# dboard_eagle_1.net
KiCad netlist of a schematic drawn in Altium Designer
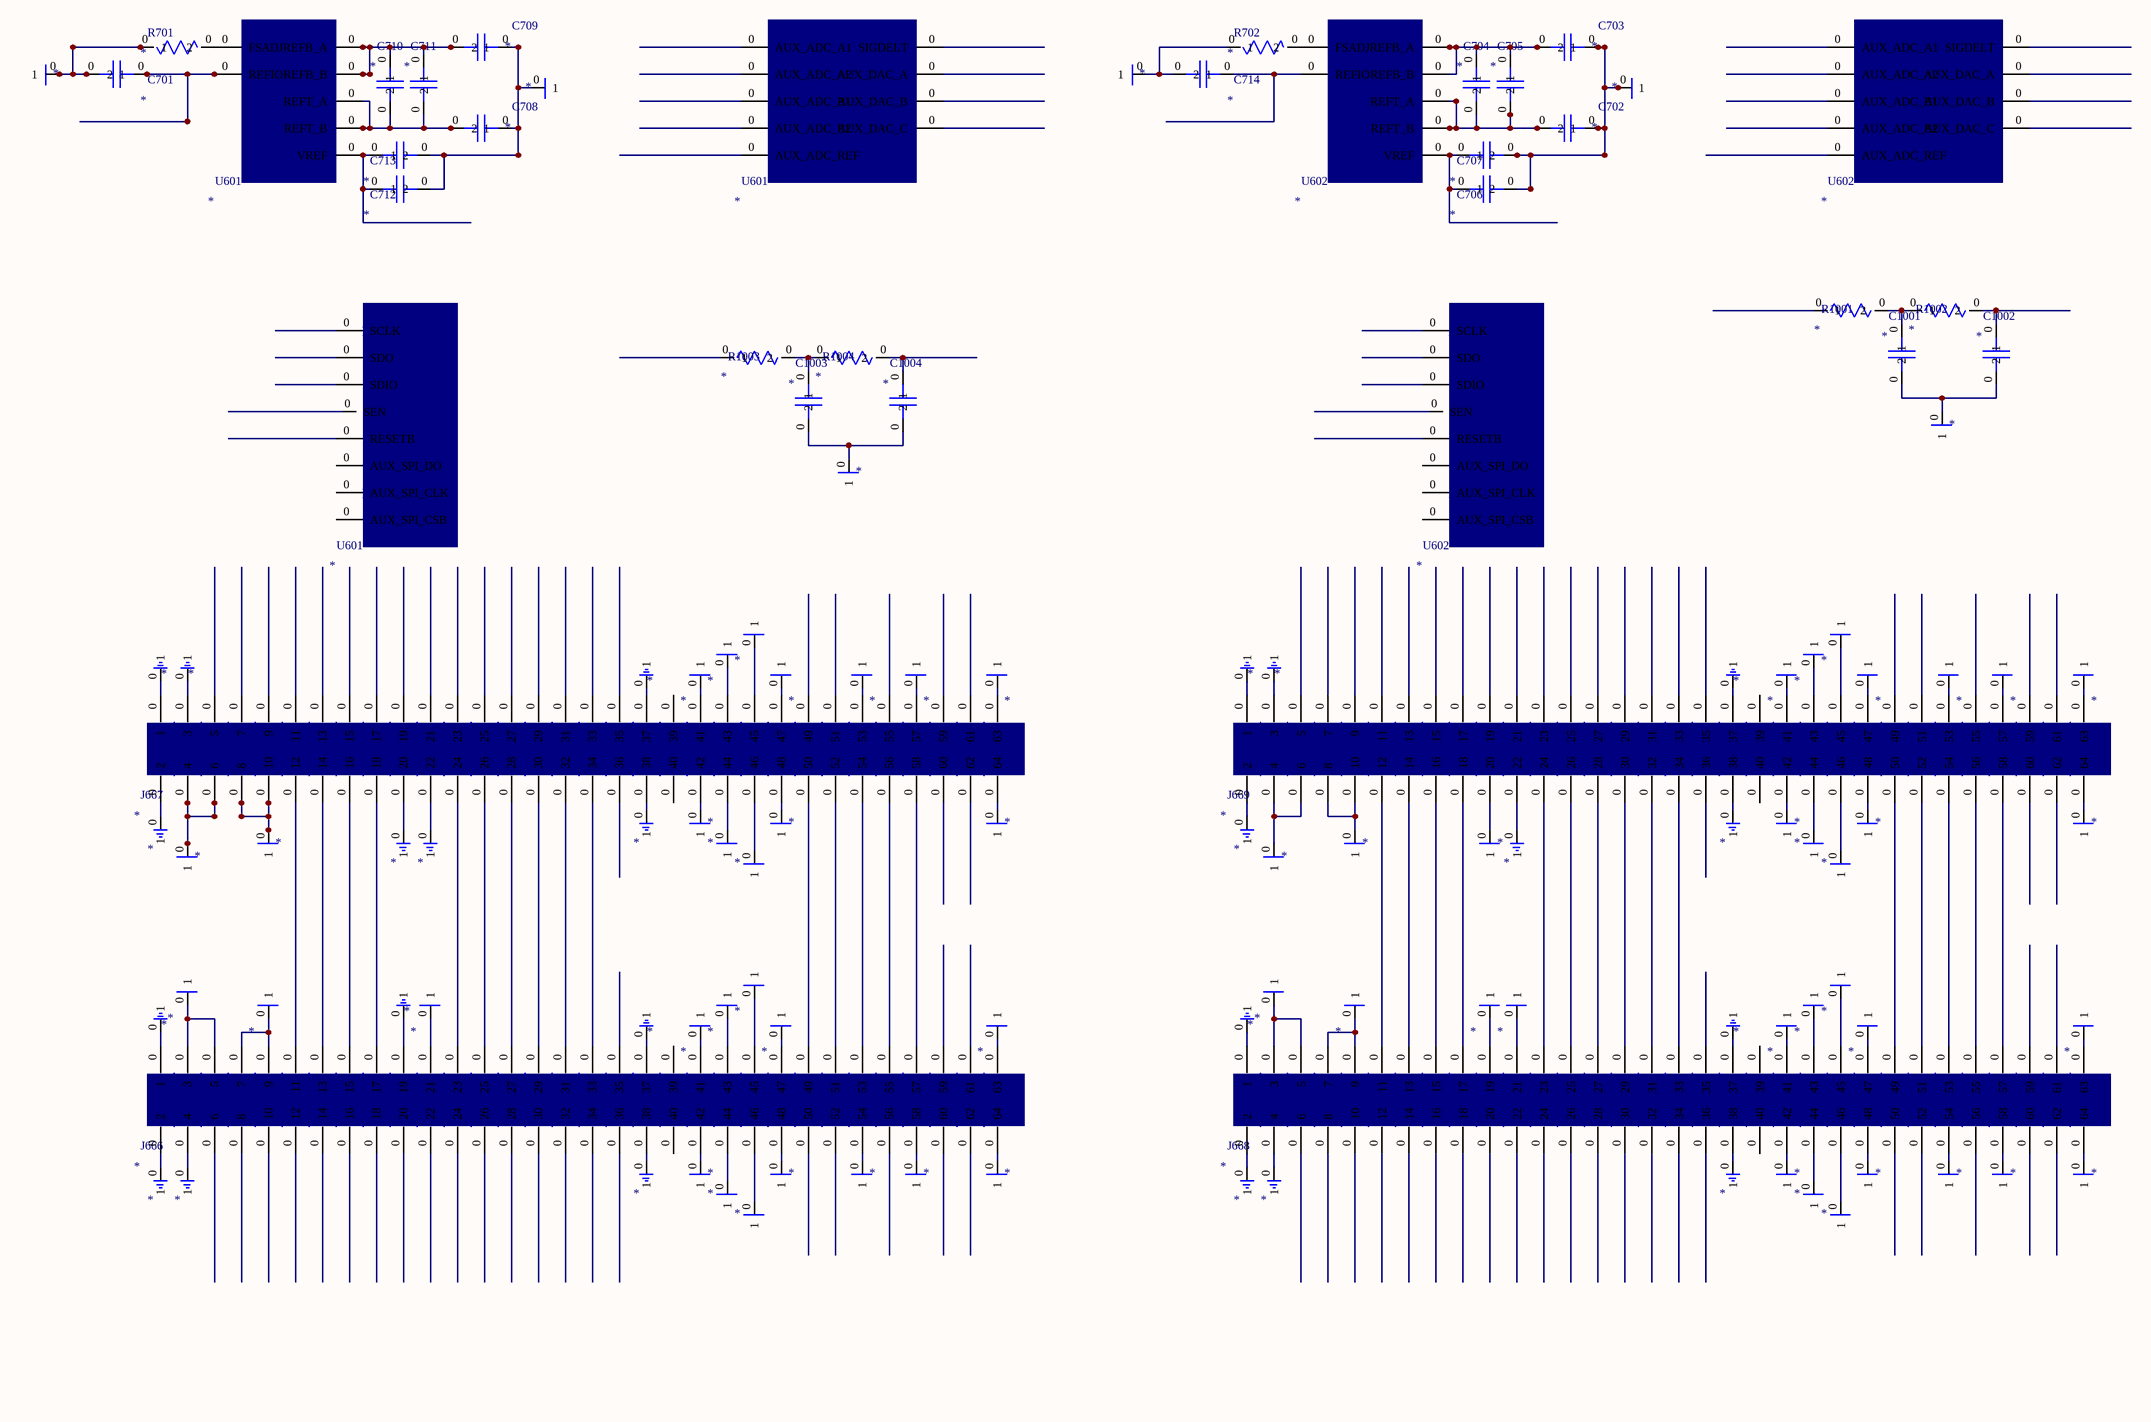
[diagram p0: dboard_eagle_1.SchDoc]

(export (version "E")
  (design (tool "Eeschema 10.0.6"))
  (components
    (comp (ref "C701") (value "*") (libsource (lib "") (part "CAPACITOR-1_MIRRORED_1")))
    (comp (ref "C702") (value "*") (libsource (lib "") (part "CAPACITOR-1_15")))
    (comp (ref "C703") (value "*") (libsource (lib "") (part "CAPACITOR-1_8")))
    (comp (ref "C704") (value "*") (libsource (lib "") (part "CAPACITOR-1_10")))
    (comp (ref "C705") (value "*") (libsource (lib "") (part "CAPACITOR-1_3")))
    (comp (ref "C706") (value "*") (libsource (lib "") (part "CAPACITOR-1_7")))
    (comp (ref "C707") (value "*") (libsource (lib "") (part "CAPACITOR-1_14")))
    (comp (ref "C708") (value "*") (libsource (lib "") (part "CAPACITOR-1_5")))
    (comp (ref "C709") (value "*") (libsource (lib "") (part "CAPACITOR-1_13")))
    (comp (ref "C710") (value "*") (libsource (lib "") (part "CAPACITOR-1_4")))
    (comp (ref "C711") (value "*") (libsource (lib "openjson") (part "CAPACITOR-1")))
    (comp (ref "C712") (value "*") (libsource (lib "") (part "CAPACITOR-1_1")))
    (comp (ref "C713") (value "*") (libsource (lib "") (part "CAPACITOR-1_9")))
    (comp (ref "C714") (value "*") (libsource (lib "openjson") (part "CAPACITOR-1_MIRRORED")))
    (comp (ref "C1001") (value "*") (libsource (lib "") (part "CAPACITOR-1_6")))
    (comp (ref "C1002") (value "*") (libsource (lib "") (part "CAPACITOR-1_11")))
    (comp (ref "C1003") (value "*") (libsource (lib "") (part "CAPACITOR-1_12")))
    (comp (ref "C1004") (value "*") (libsource (lib "") (part "CAPACITOR-1_2")))
    (comp (ref "GENERIC-POWER") (value "*") (libsource (lib "openjson") (part "GENERIC-POWER")))
    (comp (ref "GENERIC-POWER-2") (value "*") (libsource (lib "openjson") (part "GENERIC-POWER")))
    (comp (ref "GENERIC-POWER-3") (value "*") (libsource (lib "openjson") (part "GENERIC-POWER")))
    (comp (ref "GENERIC-POWER-4") (value "*") (libsource (lib "") (part "GENERIC-POWER_1")))
    (comp (ref "GENERIC-POWER-9") (value "*") (libsource (lib "openjson") (part "GENERIC-POWER")))
    (comp (ref "GENERIC-POWER-10") (value "*") (libsource (lib "") (part "GENERIC-POWER_1")))
    (comp (ref "GENERIC-POWER-15") (value "*") (libsource (lib "openjson") (part "GENERIC-POWER")))
    (comp (ref "GENERIC-POWER-16") (value "*") (libsource (lib "openjson") (part "GENERIC-POWER")))
    (comp (ref "GENERIC-POWER-17") (value "*") (libsource (lib "") (part "GENERIC-POWER_1")))
    (comp (ref "GENERIC-POWER-18") (value "*") (libsource (lib "") (part "GENERIC-POWER_1")))
    (comp (ref "GENERIC-POWER-19") (value "*") (libsource (lib "openjson") (part "GENERIC-POWER")))
    (comp (ref "GENERIC-POWER-20") (value "*") (libsource (lib "openjson") (part "GENERIC-POWER")))
    (comp (ref "GENERIC-POWER-21") (value "*") (libsource (lib "openjson") (part "GENERIC-POWER")))
    (comp (ref "GENERIC-POWER-26") (value "*") (libsource (lib "openjson") (part "GENERIC-POWER")))
    (comp (ref "GENERIC-POWER-27") (value "*") (libsource (lib "") (part "GENERIC-POWER_1")))
    (comp (ref "GENERIC-POWER-28") (value "*") (libsource (lib "") (part "GENERIC-POWER_1")))
    (comp (ref "GENERIC-POWER-29") (value "*") (libsource (lib "") (part "GENERIC-POWER_1")))
    (comp (ref "GENERIC-POWER-32") (value "*") (libsource (lib "") (part "GENERIC-POWER_1")))
    (comp (ref "GENERIC-POWER-35") (value "*") (libsource (lib "") (part "GENERIC-POWER_1")))
    (comp (ref "GENERIC-POWER-36") (value "*") (libsource (lib "") (part "GENERIC-POWER_1")))
    (comp (ref "GENERIC-POWER-37") (value "*") (libsource (lib "openjson") (part "GENERIC-POWER")))
    (comp (ref "GENERIC-POWER-38") (value "*") (libsource (lib "") (part "GENERIC-POWER_1")))
    (comp (ref "GENERIC-POWER-42") (value "*") (libsource (lib "openjson") (part "GENERIC-POWER")))
    (comp (ref "GENERIC-POWER-43") (value "*") (libsource (lib "openjson") (part "GENERIC-POWER")))
    (comp (ref "GENERIC-POWER-44") (value "*") (libsource (lib "openjson") (part "GENERIC-POWER")))
    (comp (ref "GENERIC-POWER-48") (value "*") (libsource (lib "") (part "GENERIC-POWER_1")))
    (comp (ref "GENERIC-POWER-53") (value "*") (libsource (lib "openjson") (part "GENERIC-POWER")))
    (comp (ref "GENERIC-POWER-54") (value "*") (libsource (lib "") (part "GENERIC-POWER_1")))
    (comp (ref "GENERIC-POWER-59") (value "*") (libsource (lib "openjson") (part "GENERIC-POWER")))
    (comp (ref "GENERIC-POWER-60") (value "*") (libsource (lib "openjson") (part "GENERIC-POWER")))
    (comp (ref "GENERIC-POWER-61") (value "*") (libsource (lib "") (part "GENERIC-POWER_1")))
    (comp (ref "GENERIC-POWER-62") (value "*") (libsource (lib "") (part "GENERIC-POWER_1")))
    (comp (ref "GENERIC-POWER-63") (value "*") (libsource (lib "openjson") (part "GENERIC-POWER")))
    (comp (ref "GENERIC-POWER-64") (value "*") (libsource (lib "openjson") (part "GENERIC-POWER")))
    (comp (ref "GENERIC-POWER-65") (value "*") (libsource (lib "openjson") (part "GENERIC-POWER")))
    (comp (ref "GENERIC-POWER-70") (value "*") (libsource (lib "openjson") (part "GENERIC-POWER")))
    (comp (ref "GENERIC-POWER-71") (value "*") (libsource (lib "") (part "GENERIC-POWER_1")))
    (comp (ref "GENERIC-POWER-72") (value "*") (libsource (lib "") (part "GENERIC-POWER_1")))
    (comp (ref "GENERIC-POWER-73") (value "*") (libsource (lib "") (part "GENERIC-POWER_1")))
    (comp (ref "GENERIC-POWER-76") (value "*") (libsource (lib "") (part "GENERIC-POWER_1")))
    (comp (ref "GENERIC-POWER-79") (value "*") (libsource (lib "") (part "GENERIC-POWER_1")))
    (comp (ref "GENERIC-POWER-80") (value "*") (libsource (lib "") (part "GENERIC-POWER_1")))
    (comp (ref "GENERIC-POWER-81") (value "*") (libsource (lib "openjson") (part "GENERIC-POWER")))
    (comp (ref "GENERIC-POWER-82") (value "*") (libsource (lib "") (part "GENERIC-POWER_1")))
    (comp (ref "GENERIC-POWER-83") (value "*") (libsource (lib "") (part "GENERIC-POWER_1")))
    (comp (ref "GENERIC-POWER-84") (value "*") (libsource (lib "openjson") (part "GENERIC-POWER")))
    (comp (ref "GENERIC-POWER-85") (value "*") (libsource (lib "openjson") (part "GENERIC-POWER")))
    (comp (ref "GENERIC-POWER-86") (value "*") (libsource (lib "openjson") (part "GENERIC-POWER")))
    (comp (ref "GENERIC-POWER_MIRRORED") (value "*") (libsource (lib "") (part "GENERIC-POWER_MIRRORED_1")))
    (comp (ref "GENERIC-POWER_MIRRORED-22")
      (value "*")
      (libsource (lib "") (part "GENERIC-POWER_MIRRORED_1"))
    )
    (comp (ref "GENERIC-POWER_MIRRORED-23")
      (value "*")
      (libsource (lib "") (part "GENERIC-POWER_MIRRORED_1"))
    )
    (comp (ref "GENERIC-POWER_MIRRORED-24")
      (value "*")
      (libsource (lib "") (part "GENERIC-POWER_MIRRORED_1"))
    )
    (comp (ref "GENERIC-POWER_MIRRORED-25")
      (value "*")
      (libsource (lib "") (part "GENERIC-POWER_MIRRORED_1"))
    )
    (comp (ref "GENERIC-POWER_MIRRORED-30")
      (value "*")
      (libsource (lib "openjson") (part "GENERIC-POWER_MIRRORED"))
    )
    (comp (ref "GENERIC-POWER_MIRRORED-31")
      (value "*")
      (libsource (lib "openjson") (part "GENERIC-POWER_MIRRORED"))
    )
    (comp (ref "GENERIC-POWER_MIRRORED-33")
      (value "*")
      (libsource (lib "openjson") (part "GENERIC-POWER_MIRRORED"))
    )
    (comp (ref "GENERIC-POWER_MIRRORED-34")
      (value "*")
      (libsource (lib "openjson") (part "GENERIC-POWER_MIRRORED"))
    )
    (comp (ref "GENERIC-POWER_MIRRORED-41")
      (value "*")
      (libsource (lib "") (part "GENERIC-POWER_MIRRORED_1"))
    )
    (comp (ref "GENERIC-POWER_MIRRORED-66")
      (value "*")
      (libsource (lib "") (part "GENERIC-POWER_MIRRORED_1"))
    )
    (comp (ref "GENERIC-POWER_MIRRORED-67")
      (value "*")
      (libsource (lib "") (part "GENERIC-POWER_MIRRORED_1"))
    )
    (comp (ref "GENERIC-POWER_MIRRORED-68")
      (value "*")
      (libsource (lib "") (part "GENERIC-POWER_MIRRORED_1"))
    )
    (comp (ref "GENERIC-POWER_MIRRORED-69")
      (value "*")
      (libsource (lib "") (part "GENERIC-POWER_MIRRORED_1"))
    )
    (comp (ref "GENERIC-POWER_MIRRORED-74")
      (value "*")
      (libsource (lib "openjson") (part "GENERIC-POWER_MIRRORED"))
    )
    (comp (ref "GENERIC-POWER_MIRRORED-75")
      (value "*")
      (libsource (lib "openjson") (part "GENERIC-POWER_MIRRORED"))
    )
    (comp (ref "GENERIC-POWER_MIRRORED-77")
      (value "*")
      (libsource (lib "openjson") (part "GENERIC-POWER_MIRRORED"))
    )
    (comp (ref "GENERIC-POWER_MIRRORED-78")
      (value "*")
      (libsource (lib "openjson") (part "GENERIC-POWER_MIRRORED"))
    )
    (comp (ref "GND-1") (value "*") (libsource (lib "openjson") (part "GND-1")))
    (comp (ref "GND-1-5") (value "*") (libsource (lib "") (part "GND-1_1")))
    (comp (ref "GND-1-6") (value "*") (libsource (lib "") (part "GND-1_1")))
    (comp (ref "GND-1-7") (value "*") (libsource (lib "openjson") (part "GND-1")))
    (comp (ref "GND-1-8") (value "*") (libsource (lib "openjson") (part "GND-1")))
    (comp (ref "GND-1-11") (value "*") (libsource (lib "openjson") (part "GND-1")))
    (comp (ref "GND-1-12") (value "*") (libsource (lib "") (part "GND-1_1")))
    (comp (ref "GND-1-13") (value "*") (libsource (lib "openjson") (part "GND-1")))
    (comp (ref "GND-1-14") (value "*") (libsource (lib "") (part "GND-1_1")))
    (comp (ref "GND-1-45") (value "*") (libsource (lib "openjson") (part "GND-1")))
    (comp (ref "GND-1-46") (value "*") (libsource (lib "openjson") (part "GND-1")))
    (comp (ref "GND-1-47") (value "*") (libsource (lib "") (part "GND-1_1")))
    (comp (ref "GND-1-49") (value "*") (libsource (lib "") (part "GND-1_1")))
    (comp (ref "GND-1-50") (value "*") (libsource (lib "") (part "GND-1_1")))
    (comp (ref "GND-1-51") (value "*") (libsource (lib "openjson") (part "GND-1")))
    (comp (ref "GND-1-52") (value "*") (libsource (lib "openjson") (part "GND-1")))
    (comp (ref "GND-1-55") (value "*") (libsource (lib "openjson") (part "GND-1")))
    (comp (ref "GND-1-56") (value "*") (libsource (lib "") (part "GND-1_1")))
    (comp (ref "GND-1-57") (value "*") (libsource (lib "openjson") (part "GND-1")))
    (comp (ref "GND-1-58") (value "*") (libsource (lib "") (part "GND-1_1")))
    (comp (ref "GND-1-87") (value "*") (libsource (lib "") (part "GND-1_1")))
    (comp (ref "GND-1-88") (value "*") (libsource (lib "openjson") (part "GND-1")))
    (comp (ref "GND-1-89") (value "*") (libsource (lib "") (part "GND-1_1")))
    (comp (ref "GND-1-90") (value "*") (libsource (lib "openjson") (part "GND-1")))
    (comp (ref "J666") (value "*") (libsource (lib "") (part "PMC64_MIRRORED_2")))
    (comp (ref "J667") (value "*") (libsource (lib "") (part "PMC64_MIRRORED_1")))
    (comp (ref "J668") (value "*") (libsource (lib "") (part "PMC64_MIRRORED_3")))
    (comp (ref "J669") (value "*") (libsource (lib "openjson") (part "PMC64_MIRRORED")))
    (comp (ref "R701") (value "*") (libsource (lib "openjson") (part "RESISTOR-1_MIRRORED")))
    (comp (ref "R702") (value "*") (libsource (lib "") (part "RESISTOR-1_MIRRORED_1")))
    (comp (ref "R1001") (value "*") (libsource (lib "") (part "RESISTOR-1_2")))
    (comp (ref "R1002") (value "*") (libsource (lib "openjson") (part "RESISTOR-1")))
    (comp (ref "R1003") (value "*") (libsource (lib "") (part "RESISTOR-1_3")))
    (comp (ref "R1004") (value "*") (libsource (lib "") (part "RESISTOR-1_1")))
    (comp (ref "U601") (value "*") (libsource (lib "") (part "AD986X-ACTRL_1")))
    (comp (ref "U601-39") (value "*") (libsource (lib "") (part "AD986X-AUX_1")))
    (comp (ref "U601-40") (value "*") (libsource (lib "") (part "AD986X-CTRL_1")))
    (comp (ref "U602") (value "*") (libsource (lib "openjson") (part "AD986X-ACTRL")))
    (comp (ref "U602-0") (value "*") (libsource (lib "openjson") (part "AD986X-AUX")))
    (comp (ref "U602-1") (value "*") (libsource (lib "openjson") (part "AD986X-CTRL")))
  )
  (nets
    (net (code "1") (name "Net-(C701-1)") (class "Default")
      (node (ref "C701") (pin "0") (pinfunction "1_0") (pintype "passive"))
      (node (ref "U601") (pin "0") (pinfunction "REFIO_0") (pintype "passive"))
    )
    (net (code "2") (name "Net-(C701-2)") (class "Default")
      (node (ref "C701") (pin "0") (pinfunction "2_0") (pintype "passive"))
      (node (ref "GENERIC-POWER_MIRRORED-41") (pin "0") (pinfunction "1_0") (pintype "passive"))
      (node (ref "R701") (pin "0") (pinfunction "1_0") (pintype "passive"))
    )
    (net (code "3") (name "Net-(C702-1)") (class "Default")
      (node (ref "C702") (pin "0") (pinfunction "1_0") (pintype "passive"))
      (node (ref "C703") (pin "0") (pinfunction "1_0") (pintype "passive"))
      (node (ref "C706") (pin "0") (pinfunction "2_0") (pintype "passive"))
      (node (ref "C707") (pin "0") (pinfunction "2_0") (pintype "passive"))
      (node (ref "GENERIC-POWER") (pin "0") (pinfunction "1_0") (pintype "passive"))
    )
    (net (code "4") (name "Net-(C702-2)") (class "Default")
      (node (ref "C702") (pin "0") (pinfunction "2_0") (pintype "passive"))
      (node (ref "C704") (pin "0") (pinfunction "2_0") (pintype "passive"))
      (node (ref "C705") (pin "0") (pinfunction "2_0") (pintype "passive"))
      (node (ref "U602") (pin "0") (pinfunction "REFT_A_0") (pintype "passive"))
    )
    (net (code "5") (name "Net-(C703-2)") (class "Default")
      (node (ref "C703") (pin "0") (pinfunction "2_0") (pintype "passive"))
      (node (ref "C704") (pin "0") (pinfunction "1_0") (pintype "passive"))
      (node (ref "C705") (pin "0") (pinfunction "1_0") (pintype "passive"))
      (node (ref "U602") (pin "0") (pinfunction "REFB_A_0") (pintype "passive"))
    )
    (net (code "6") (name "Net-(C706-1)") (class "Default")
      (node (ref "C706") (pin "0") (pinfunction "1_0") (pintype "passive"))
      (node (ref "C707") (pin "0") (pinfunction "1_0") (pintype "passive"))
      (node (ref "U602") (pin "0") (pinfunction "VREF_0") (pintype "passive"))
    )
    (net (code "7") (name "Net-(C708-1)") (class "Default")
      (node (ref "C708") (pin "0") (pinfunction "1_0") (pintype "passive"))
      (node (ref "C709") (pin "0") (pinfunction "1_0") (pintype "passive"))
      (node (ref "C712") (pin "0") (pinfunction "2_0") (pintype "passive"))
      (node (ref "C713") (pin "0") (pinfunction "2_0") (pintype "passive"))
      (node (ref "GENERIC-POWER-42") (pin "0") (pinfunction "1_0") (pintype "passive"))
    )
    (net (code "8") (name "Net-(C708-2)") (class "Default")
      (node (ref "C708") (pin "0") (pinfunction "2_0") (pintype "passive"))
      (node (ref "C710") (pin "0") (pinfunction "2_0") (pintype "passive"))
      (node (ref "C711") (pin "0") (pinfunction "2_0") (pintype "passive"))
      (node (ref "U601") (pin "0") (pinfunction "REFT_A_0") (pintype "passive"))
    )
    (net (code "9") (name "Net-(C709-2)") (class "Default")
      (node (ref "C709") (pin "0") (pinfunction "2_0") (pintype "passive"))
      (node (ref "C710") (pin "0") (pinfunction "1_0") (pintype "passive"))
      (node (ref "C711") (pin "0") (pinfunction "1_0") (pintype "passive"))
      (node (ref "U601") (pin "0") (pinfunction "REFB_A_0") (pintype "passive"))
    )
    (net (code "10") (name "Net-(C712-1)") (class "Default")
      (node (ref "C712") (pin "0") (pinfunction "1_0") (pintype "passive"))
      (node (ref "C713") (pin "0") (pinfunction "1_0") (pintype "passive"))
      (node (ref "U601") (pin "0") (pinfunction "VREF_0") (pintype "passive"))
    )
    (net (code "11") (name "Net-(C714-1)") (class "Default")
      (node (ref "C714") (pin "0") (pinfunction "1_0") (pintype "passive"))
      (node (ref "U602") (pin "0") (pinfunction "REFIO_0") (pintype "passive"))
    )
    (net (code "12") (name "Net-(C714-2)") (class "Default")
      (node (ref "C714") (pin "0") (pinfunction "2_0") (pintype "passive"))
      (node (ref "GENERIC-POWER_MIRRORED") (pin "0") (pinfunction "1_0") (pintype "passive"))
      (node (ref "R702") (pin "0") (pinfunction "1_0") (pintype "passive"))
    )
    (net (code "13") (name "Net-(C1001-1)") (class "Default")
      (node (ref "C1001") (pin "0") (pinfunction "1_0") (pintype "passive"))
      (node (ref "R1001") (pin "0") (pinfunction "2_0") (pintype "passive"))
      (node (ref "R1002") (pin "0") (pinfunction "1_0") (pintype "passive"))
    )
    (net (code "14") (name "Net-(C1001-2)") (class "Default")
      (node (ref "C1001") (pin "0") (pinfunction "2_0") (pintype "passive"))
      (node (ref "C1002") (pin "0") (pinfunction "2_0") (pintype "passive"))
      (node (ref "GENERIC-POWER-85") (pin "0") (pinfunction "1_0") (pintype "passive"))
    )
    (net (code "15") (name "Net-(C1002-1)") (class "Default")
      (node (ref "C1002") (pin "0") (pinfunction "1_0") (pintype "passive"))
      (node (ref "R1002") (pin "0") (pinfunction "2_0") (pintype "passive"))
    )
    (net (code "16") (name "Net-(C1003-1)") (class "Default")
      (node (ref "C1003") (pin "0") (pinfunction "1_0") (pintype "passive"))
      (node (ref "R1003") (pin "0") (pinfunction "2_0") (pintype "passive"))
      (node (ref "R1004") (pin "0") (pinfunction "1_0") (pintype "passive"))
    )
    (net (code "17") (name "Net-(C1003-2)") (class "Default")
      (node (ref "C1003") (pin "0") (pinfunction "2_0") (pintype "passive"))
      (node (ref "C1004") (pin "0") (pinfunction "2_0") (pintype "passive"))
      (node (ref "GENERIC-POWER-86") (pin "0") (pinfunction "1_0") (pintype "passive"))
    )
    (net (code "18") (name "Net-(C1004-1)") (class "Default")
      (node (ref "C1004") (pin "0") (pinfunction "1_0") (pintype "passive"))
      (node (ref "R1004") (pin "0") (pinfunction "2_0") (pintype "passive"))
    )
    (net (code "19") (name "Net-(GENERIC-POWER-2-1)") (class "Default")
      (node (ref "GENERIC-POWER-2") (pin "0") (pinfunction "1_0") (pintype "passive"))
      (node (ref "J668") (pin "0") (pinfunction "64_0") (pintype "passive"))
    )
    (net (code "20") (name "Net-(GENERIC-POWER-3-1)") (class "Default")
      (node (ref "GENERIC-POWER-3") (pin "0") (pinfunction "1_0") (pintype "passive"))
      (node (ref "J669") (pin "0") (pinfunction "10_0") (pintype "passive"))
    )
    (net (code "21") (name "Net-(GENERIC-POWER-4-1)") (class "Default")
      (node (ref "GENERIC-POWER-4") (pin "0") (pinfunction "1_0") (pintype "passive"))
      (node (ref "J668") (pin "0") (pinfunction "21_0") (pintype "passive"))
    )
    (net (code "22") (name "Net-(GENERIC-POWER-9-1)") (class "Default")
      (node (ref "GENERIC-POWER-9") (pin "0") (pinfunction "1_0") (pintype "passive"))
      (node (ref "J669") (pin "0") (pinfunction "64_0") (pintype "passive"))
    )
    (net (code "23") (name "Net-(GENERIC-POWER-10-1)") (class "Default")
      (node (ref "GENERIC-POWER-10") (pin "0") (pinfunction "1_0") (pintype "passive"))
      (node (ref "J668") (pin "0") (pinfunction "63_0") (pintype "passive"))
    )
    (net (code "24") (name "Net-(GENERIC-POWER-15-1)") (class "Default")
      (node (ref "GENERIC-POWER-15") (pin "0") (pinfunction "1_0") (pintype "passive"))
      (node (ref "J668") (pin "0") (pinfunction "42_0") (pintype "passive"))
    )
    (net (code "25") (name "Net-(GENERIC-POWER-16-1)") (class "Default")
      (node (ref "GENERIC-POWER-16") (pin "0") (pinfunction "1_0") (pintype "passive"))
      (node (ref "J669") (pin "0") (pinfunction "42_0") (pintype "passive"))
    )
    (net (code "26") (name "Net-(GENERIC-POWER-17-1)") (class "Default")
      (node (ref "GENERIC-POWER-17") (pin "0") (pinfunction "1_0") (pintype "passive"))
      (node (ref "J669") (pin "0") (pinfunction "41_0") (pintype "passive"))
    )
    (net (code "27") (name "Net-(GENERIC-POWER-18-1)") (class "Default")
      (node (ref "GENERIC-POWER-18") (pin "0") (pinfunction "1_0") (pintype "passive"))
      (node (ref "J668") (pin "0") (pinfunction "41_0") (pintype "passive"))
    )
    (net (code "28") (name "Net-(GENERIC-POWER-19-1)") (class "Default")
      (node (ref "GENERIC-POWER-19") (pin "0") (pinfunction "1_0") (pintype "passive"))
      (node (ref "J668") (pin "0") (pinfunction "58_0") (pintype "passive"))
    )
    (net (code "29") (name "Net-(GENERIC-POWER-20-1)") (class "Default")
      (node (ref "GENERIC-POWER-20") (pin "0") (pinfunction "1_0") (pintype "passive"))
      (node (ref "J668") (pin "0") (pinfunction "54_0") (pintype "passive"))
    )
    (net (code "30") (name "Net-(GENERIC-POWER-21-1)") (class "Default")
      (node (ref "GENERIC-POWER-21") (pin "0") (pinfunction "1_0") (pintype "passive"))
      (node (ref "J668") (pin "0") (pinfunction "48_0") (pintype "passive"))
    )
    (net (code "31") (name "Net-(GENERIC-POWER-26-1)") (class "Default")
      (node (ref "GENERIC-POWER-26") (pin "0") (pinfunction "1_0") (pintype "passive"))
      (node (ref "J669") (pin "0") (pinfunction "48_0") (pintype "passive"))
    )
    (net (code "32") (name "Net-(GENERIC-POWER-27-1)") (class "Default")
      (node (ref "GENERIC-POWER-27") (pin "0") (pinfunction "1_0") (pintype "passive"))
      (node (ref "J668") (pin "0") (pinfunction "47_0") (pintype "passive"))
    )
    (net (code "33") (name "Net-(GENERIC-POWER-28-1)") (class "Default")
      (node (ref "GENERIC-POWER-28") (pin "0") (pinfunction "1_0") (pintype "passive"))
      (node (ref "J668") (pin "0") (pinfunction "45_0") (pintype "passive"))
    )
    (net (code "34") (name "Net-(GENERIC-POWER-29-1)") (class "Default")
      (node (ref "GENERIC-POWER-29") (pin "0") (pinfunction "1_0") (pintype "passive"))
      (node (ref "J668") (pin "0") (pinfunction "43_0") (pintype "passive"))
    )
    (net (code "35") (name "Net-(GENERIC-POWER-32-1)") (class "Default")
      (node (ref "GENERIC-POWER-32") (pin "0") (pinfunction "1_0") (pintype "passive"))
      (node (ref "J668") (pin "0") (pinfunction "5_0") (pintype "passive"))
    )
    (net (code "36") (name "Net-(GENERIC-POWER-35-1)") (class "Default")
      (node (ref "GENERIC-POWER-35") (pin "0") (pinfunction "1_0") (pintype "passive"))
      (node (ref "J669") (pin "0") (pinfunction "43_0") (pintype "passive"))
    )
    (net (code "37") (name "Net-(GENERIC-POWER-36-1)") (class "Default")
      (node (ref "GENERIC-POWER-36") (pin "0") (pinfunction "1_0") (pintype "passive"))
      (node (ref "J669") (pin "0") (pinfunction "45_0") (pintype "passive"))
    )
    (net (code "38") (name "Net-(GENERIC-POWER-37-1)") (class "Default")
      (node (ref "GENERIC-POWER-37") (pin "0") (pinfunction "1_0") (pintype "passive"))
      (node (ref "J669") (pin "0") (pinfunction "6_0") (pintype "passive"))
    )
    (net (code "39") (name "Net-(GENERIC-POWER-38-1)") (class "Default")
      (node (ref "GENERIC-POWER-38") (pin "0") (pinfunction "1_0") (pintype "passive"))
      (node (ref "J668") (pin "0") (pinfunction "9_0") (pintype "passive"))
    )
    (net (code "40") (name "Net-(GENERIC-POWER-43-1)") (class "Default")
      (node (ref "GENERIC-POWER-43") (pin "0") (pinfunction "1_0") (pintype "passive"))
      (node (ref "J666") (pin "0") (pinfunction "64_0") (pintype "passive"))
    )
    (net (code "41") (name "Net-(GENERIC-POWER-44-1)") (class "Default")
      (node (ref "GENERIC-POWER-44") (pin "0") (pinfunction "1_0") (pintype "passive"))
      (node (ref "J667") (pin "0") (pinfunction "10_0") (pintype "passive"))
    )
    (net (code "42") (name "Net-(GENERIC-POWER-48-1)") (class "Default")
      (node (ref "GENERIC-POWER-48") (pin "0") (pinfunction "1_0") (pintype "passive"))
      (node (ref "J666") (pin "0") (pinfunction "21_0") (pintype "passive"))
    )
    (net (code "43") (name "Net-(GENERIC-POWER-53-1)") (class "Default")
      (node (ref "GENERIC-POWER-53") (pin "0") (pinfunction "1_0") (pintype "passive"))
      (node (ref "J667") (pin "0") (pinfunction "64_0") (pintype "passive"))
    )
    (net (code "44") (name "Net-(GENERIC-POWER-54-1)") (class "Default")
      (node (ref "GENERIC-POWER-54") (pin "0") (pinfunction "1_0") (pintype "passive"))
      (node (ref "J666") (pin "0") (pinfunction "63_0") (pintype "passive"))
    )
    (net (code "45") (name "Net-(GENERIC-POWER-59-1)") (class "Default")
      (node (ref "GENERIC-POWER-59") (pin "0") (pinfunction "1_0") (pintype "passive"))
      (node (ref "J666") (pin "0") (pinfunction "42_0") (pintype "passive"))
    )
    (net (code "46") (name "Net-(GENERIC-POWER-60-1)") (class "Default")
      (node (ref "GENERIC-POWER-60") (pin "0") (pinfunction "1_0") (pintype "passive"))
      (node (ref "J667") (pin "0") (pinfunction "42_0") (pintype "passive"))
    )
    (net (code "47") (name "Net-(GENERIC-POWER-61-1)") (class "Default")
      (node (ref "GENERIC-POWER-61") (pin "0") (pinfunction "1_0") (pintype "passive"))
      (node (ref "J667") (pin "0") (pinfunction "41_0") (pintype "passive"))
    )
    (net (code "48") (name "Net-(GENERIC-POWER-62-1)") (class "Default")
      (node (ref "GENERIC-POWER-62") (pin "0") (pinfunction "1_0") (pintype "passive"))
      (node (ref "J666") (pin "0") (pinfunction "41_0") (pintype "passive"))
    )
    (net (code "49") (name "Net-(GENERIC-POWER-63-1)") (class "Default")
      (node (ref "GENERIC-POWER-63") (pin "0") (pinfunction "1_0") (pintype "passive"))
      (node (ref "J666") (pin "0") (pinfunction "58_0") (pintype "passive"))
    )
    (net (code "50") (name "Net-(GENERIC-POWER-64-1)") (class "Default")
      (node (ref "GENERIC-POWER-64") (pin "0") (pinfunction "1_0") (pintype "passive"))
      (node (ref "J666") (pin "0") (pinfunction "54_0") (pintype "passive"))
    )
    (net (code "51") (name "Net-(GENERIC-POWER-65-1)") (class "Default")
      (node (ref "GENERIC-POWER-65") (pin "0") (pinfunction "1_0") (pintype "passive"))
      (node (ref "J666") (pin "0") (pinfunction "48_0") (pintype "passive"))
    )
    (net (code "52") (name "Net-(GENERIC-POWER-70-1)") (class "Default")
      (node (ref "GENERIC-POWER-70") (pin "0") (pinfunction "1_0") (pintype "passive"))
      (node (ref "J667") (pin "0") (pinfunction "48_0") (pintype "passive"))
    )
    (net (code "53") (name "Net-(GENERIC-POWER-71-1)") (class "Default")
      (node (ref "GENERIC-POWER-71") (pin "0") (pinfunction "1_0") (pintype "passive"))
      (node (ref "J666") (pin "0") (pinfunction "47_0") (pintype "passive"))
    )
    (net (code "54") (name "Net-(GENERIC-POWER-72-1)") (class "Default")
      (node (ref "GENERIC-POWER-72") (pin "0") (pinfunction "1_0") (pintype "passive"))
      (node (ref "J666") (pin "0") (pinfunction "45_0") (pintype "passive"))
    )
    (net (code "55") (name "Net-(GENERIC-POWER-73-1)") (class "Default")
      (node (ref "GENERIC-POWER-73") (pin "0") (pinfunction "1_0") (pintype "passive"))
      (node (ref "J666") (pin "0") (pinfunction "43_0") (pintype "passive"))
    )
    (net (code "56") (name "Net-(GENERIC-POWER-76-1)") (class "Default")
      (node (ref "GENERIC-POWER-76") (pin "0") (pinfunction "1_0") (pintype "passive"))
      (node (ref "J666") (pin "0") (pinfunction "5_0") (pintype "passive"))
    )
    (net (code "57") (name "Net-(GENERIC-POWER-79-1)") (class "Default")
      (node (ref "GENERIC-POWER-79") (pin "0") (pinfunction "1_0") (pintype "passive"))
      (node (ref "J667") (pin "0") (pinfunction "43_0") (pintype "passive"))
    )
    (net (code "58") (name "Net-(GENERIC-POWER-80-1)") (class "Default")
      (node (ref "GENERIC-POWER-80") (pin "0") (pinfunction "1_0") (pintype "passive"))
      (node (ref "J667") (pin "0") (pinfunction "45_0") (pintype "passive"))
    )
    (net (code "59") (name "Net-(GENERIC-POWER-81-1)") (class "Default")
      (node (ref "GENERIC-POWER-81") (pin "0") (pinfunction "1_0") (pintype "passive"))
      (node (ref "J667") (pin "0") (pinfunction "6_0") (pintype "passive"))
    )
    (net (code "60") (name "Net-(GENERIC-POWER-82-1)") (class "Default")
      (node (ref "GENERIC-POWER-82") (pin "0") (pinfunction "1_0") (pintype "passive"))
      (node (ref "J666") (pin "0") (pinfunction "9_0") (pintype "passive"))
    )
    (net (code "61") (name "Net-(GENERIC-POWER-83-1)") (class "Default")
      (node (ref "GENERIC-POWER-83") (pin "0") (pinfunction "1_0") (pintype "passive"))
      (node (ref "J668") (pin "0") (pinfunction "19_0") (pintype "passive"))
    )
    (net (code "62") (name "Net-(GENERIC-POWER-84-1)") (class "Default")
      (node (ref "GENERIC-POWER-84") (pin "0") (pinfunction "1_0") (pintype "passive"))
      (node (ref "J669") (pin "0") (pinfunction "20_0") (pintype "passive"))
    )
    (net (code "63") (name "Net-(GENERIC-POWER_MIRRORED-22-1)") (class "Default")
      (node (ref "GENERIC-POWER_MIRRORED-22") (pin "0") (pinfunction "1_0") (pintype "passive"))
      (node (ref "J669") (pin "0") (pinfunction "63_0") (pintype "passive"))
    )
    (net (code "64") (name "Net-(GENERIC-POWER_MIRRORED-23-1)") (class "Default")
      (node (ref "GENERIC-POWER_MIRRORED-23") (pin "0") (pinfunction "1_0") (pintype "passive"))
      (node (ref "J669") (pin "0") (pinfunction "57_0") (pintype "passive"))
    )
    (net (code "65") (name "Net-(GENERIC-POWER_MIRRORED-24-1)") (class "Default")
      (node (ref "GENERIC-POWER_MIRRORED-24") (pin "0") (pinfunction "1_0") (pintype "passive"))
      (node (ref "J669") (pin "0") (pinfunction "53_0") (pintype "passive"))
    )
    (net (code "66") (name "Net-(GENERIC-POWER_MIRRORED-25-1)") (class "Default")
      (node (ref "GENERIC-POWER_MIRRORED-25") (pin "0") (pinfunction "1_0") (pintype "passive"))
      (node (ref "J669") (pin "0") (pinfunction "47_0") (pintype "passive"))
    )
    (net (code "67") (name "Net-(GENERIC-POWER_MIRRORED-30-1)") (class "Default")
      (node (ref "GENERIC-POWER_MIRRORED-30") (pin "0") (pinfunction "1_0") (pintype "passive"))
      (node (ref "J669") (pin "0") (pinfunction "46_0") (pintype "passive"))
    )
    (net (code "68") (name "Net-(GENERIC-POWER_MIRRORED-31-1)") (class "Default")
      (node (ref "GENERIC-POWER_MIRRORED-31") (pin "0") (pinfunction "1_0") (pintype "passive"))
      (node (ref "J669") (pin "0") (pinfunction "44_0") (pintype "passive"))
    )
    (net (code "69") (name "Net-(GENERIC-POWER_MIRRORED-33-1)") (class "Default")
      (node (ref "GENERIC-POWER_MIRRORED-33") (pin "0") (pinfunction "1_0") (pintype "passive"))
      (node (ref "J668") (pin "0") (pinfunction "46_0") (pintype "passive"))
    )
    (net (code "70") (name "Net-(GENERIC-POWER_MIRRORED-34-1)") (class "Default")
      (node (ref "GENERIC-POWER_MIRRORED-34") (pin "0") (pinfunction "1_0") (pintype "passive"))
      (node (ref "J668") (pin "0") (pinfunction "44_0") (pintype "passive"))
    )
    (net (code "71") (name "Net-(GENERIC-POWER_MIRRORED-66-1)") (class "Default")
      (node (ref "GENERIC-POWER_MIRRORED-66") (pin "0") (pinfunction "1_0") (pintype "passive"))
      (node (ref "J667") (pin "0") (pinfunction "63_0") (pintype "passive"))
    )
    (net (code "72") (name "Net-(GENERIC-POWER_MIRRORED-67-1)") (class "Default")
      (node (ref "GENERIC-POWER_MIRRORED-67") (pin "0") (pinfunction "1_0") (pintype "passive"))
      (node (ref "J667") (pin "0") (pinfunction "57_0") (pintype "passive"))
    )
    (net (code "73") (name "Net-(GENERIC-POWER_MIRRORED-68-1)") (class "Default")
      (node (ref "GENERIC-POWER_MIRRORED-68") (pin "0") (pinfunction "1_0") (pintype "passive"))
      (node (ref "J667") (pin "0") (pinfunction "53_0") (pintype "passive"))
    )
    (net (code "74") (name "Net-(GENERIC-POWER_MIRRORED-69-1)") (class "Default")
      (node (ref "GENERIC-POWER_MIRRORED-69") (pin "0") (pinfunction "1_0") (pintype "passive"))
      (node (ref "J667") (pin "0") (pinfunction "47_0") (pintype "passive"))
    )
    (net (code "75") (name "Net-(GENERIC-POWER_MIRRORED-74-1)") (class "Default")
      (node (ref "GENERIC-POWER_MIRRORED-74") (pin "0") (pinfunction "1_0") (pintype "passive"))
      (node (ref "J667") (pin "0") (pinfunction "46_0") (pintype "passive"))
    )
    (net (code "76") (name "Net-(GENERIC-POWER_MIRRORED-75-1)") (class "Default")
      (node (ref "GENERIC-POWER_MIRRORED-75") (pin "0") (pinfunction "1_0") (pintype "passive"))
      (node (ref "J667") (pin "0") (pinfunction "44_0") (pintype "passive"))
    )
    (net (code "77") (name "Net-(GENERIC-POWER_MIRRORED-77-1)") (class "Default")
      (node (ref "GENERIC-POWER_MIRRORED-77") (pin "0") (pinfunction "1_0") (pintype "passive"))
      (node (ref "J666") (pin "0") (pinfunction "46_0") (pintype "passive"))
    )
    (net (code "78") (name "Net-(GENERIC-POWER_MIRRORED-78-1)") (class "Default")
      (node (ref "GENERIC-POWER_MIRRORED-78") (pin "0") (pinfunction "1_0") (pintype "passive"))
      (node (ref "J666") (pin "0") (pinfunction "44_0") (pintype "passive"))
    )
    (net (code "79") (name "Net-(GND-1-1)") (class "Default")
      (node (ref "GND-1") (pin "0") (pinfunction "1_0") (pintype "passive"))
      (node (ref "J669") (pin "0") (pinfunction "22_0") (pintype "passive"))
    )
    (net (code "80") (name "Net-(GND-1-5-1)") (class "Default")
      (node (ref "GND-1-5") (pin "0") (pinfunction "1_0") (pintype "passive"))
      (node (ref "J668") (pin "0") (pinfunction "1_0") (pintype "passive"))
    )
    (net (code "81") (name "Net-(GND-1-6-1)") (class "Default")
      (node (ref "GND-1-6") (pin "0") (pinfunction "1_0") (pintype "passive"))
      (node (ref "J669") (pin "0") (pinfunction "1_0") (pintype "passive"))
    )
    (net (code "82") (name "Net-(GND-1-7-1)") (class "Default")
      (node (ref "GND-1-7") (pin "0") (pinfunction "1_0") (pintype "passive"))
      (node (ref "J669") (pin "0") (pinfunction "2_0") (pintype "passive"))
    )
    (net (code "83") (name "Net-(GND-1-8-1)") (class "Default")
      (node (ref "GND-1-8") (pin "0") (pinfunction "1_0") (pintype "passive"))
      (node (ref "J668") (pin "0") (pinfunction "2_0") (pintype "passive"))
    )
    (net (code "84") (name "Net-(GND-1-11-1)") (class "Default")
      (node (ref "GND-1-11") (pin "0") (pinfunction "1_0") (pintype "passive"))
      (node (ref "J668") (pin "0") (pinfunction "38_0") (pintype "passive"))
    )
    (net (code "85") (name "Net-(GND-1-12-1)") (class "Default")
      (node (ref "GND-1-12") (pin "0") (pinfunction "1_0") (pintype "passive"))
      (node (ref "J669") (pin "0") (pinfunction "37_0") (pintype "passive"))
    )
    (net (code "86") (name "Net-(GND-1-13-1)") (class "Default")
      (node (ref "GND-1-13") (pin "0") (pinfunction "1_0") (pintype "passive"))
      (node (ref "J669") (pin "0") (pinfunction "38_0") (pintype "passive"))
    )
    (net (code "87") (name "Net-(GND-1-14-1)") (class "Default")
      (node (ref "GND-1-14") (pin "0") (pinfunction "1_0") (pintype "passive"))
      (node (ref "J668") (pin "0") (pinfunction "37_0") (pintype "passive"))
    )
    (net (code "88") (name "Net-(GND-1-45-1)") (class "Default")
      (node (ref "GND-1-45") (pin "0") (pinfunction "1_0") (pintype "passive"))
      (node (ref "J667") (pin "0") (pinfunction "20_0") (pintype "passive"))
    )
    (net (code "89") (name "Net-(GND-1-46-1)") (class "Default")
      (node (ref "GND-1-46") (pin "0") (pinfunction "1_0") (pintype "passive"))
      (node (ref "J667") (pin "0") (pinfunction "22_0") (pintype "passive"))
    )
    (net (code "90") (name "Net-(GND-1-47-1)") (class "Default")
      (node (ref "GND-1-47") (pin "0") (pinfunction "1_0") (pintype "passive"))
      (node (ref "J666") (pin "0") (pinfunction "19_0") (pintype "passive"))
    )
    (net (code "91") (name "Net-(GND-1-49-1)") (class "Default")
      (node (ref "GND-1-49") (pin "0") (pinfunction "1_0") (pintype "passive"))
      (node (ref "J666") (pin "0") (pinfunction "1_0") (pintype "passive"))
    )
    (net (code "92") (name "Net-(GND-1-50-1)") (class "Default")
      (node (ref "GND-1-50") (pin "0") (pinfunction "1_0") (pintype "passive"))
      (node (ref "J667") (pin "0") (pinfunction "1_0") (pintype "passive"))
    )
    (net (code "93") (name "Net-(GND-1-51-1)") (class "Default")
      (node (ref "GND-1-51") (pin "0") (pinfunction "1_0") (pintype "passive"))
      (node (ref "J667") (pin "0") (pinfunction "2_0") (pintype "passive"))
    )
    (net (code "94") (name "Net-(GND-1-52-1)") (class "Default")
      (node (ref "GND-1-52") (pin "0") (pinfunction "1_0") (pintype "passive"))
      (node (ref "J666") (pin "0") (pinfunction "2_0") (pintype "passive"))
    )
    (net (code "95") (name "Net-(GND-1-55-1)") (class "Default")
      (node (ref "GND-1-55") (pin "0") (pinfunction "1_0") (pintype "passive"))
      (node (ref "J666") (pin "0") (pinfunction "38_0") (pintype "passive"))
    )
    (net (code "96") (name "Net-(GND-1-56-1)") (class "Default")
      (node (ref "GND-1-56") (pin "0") (pinfunction "1_0") (pintype "passive"))
      (node (ref "J667") (pin "0") (pinfunction "37_0") (pintype "passive"))
    )
    (net (code "97") (name "Net-(GND-1-57-1)") (class "Default")
      (node (ref "GND-1-57") (pin "0") (pinfunction "1_0") (pintype "passive"))
      (node (ref "J667") (pin "0") (pinfunction "38_0") (pintype "passive"))
    )
    (net (code "98") (name "Net-(GND-1-58-1)") (class "Default")
      (node (ref "GND-1-58") (pin "0") (pinfunction "1_0") (pintype "passive"))
      (node (ref "J666") (pin "0") (pinfunction "37_0") (pintype "passive"))
    )
    (net (code "99") (name "Net-(GND-1-87-1)") (class "Default")
      (node (ref "GND-1-87") (pin "0") (pinfunction "1_0") (pintype "passive"))
      (node (ref "J667") (pin "0") (pinfunction "3_0") (pintype "passive"))
    )
    (net (code "100") (name "Net-(GND-1-88-1)") (class "Default")
      (node (ref "GND-1-88") (pin "0") (pinfunction "1_0") (pintype "passive"))
      (node (ref "J666") (pin "0") (pinfunction "4_0") (pintype "passive"))
    )
    (net (code "101") (name "Net-(GND-1-89-1)") (class "Default")
      (node (ref "GND-1-89") (pin "0") (pinfunction "1_0") (pintype "passive"))
      (node (ref "J669") (pin "0") (pinfunction "3_0") (pintype "passive"))
    )
    (net (code "102") (name "Net-(GND-1-90-1)") (class "Default")
      (node (ref "GND-1-90") (pin "0") (pinfunction "1_0") (pintype "passive"))
      (node (ref "J668") (pin "0") (pinfunction "4_0") (pintype "passive"))
    )
    (net (code "103") (name "Net-(J666-11)") (class "Default")
      (node (ref "J666") (pin "0") (pinfunction "11_0") (pintype "passive"))
      (node (ref "J667") (pin "0") (pinfunction "12_0") (pintype "passive"))
    )
    (net (code "104") (name "Net-(J666-13)") (class "Default")
      (node (ref "J666") (pin "0") (pinfunction "13_0") (pintype "passive"))
      (node (ref "J667") (pin "0") (pinfunction "14_0") (pintype "passive"))
    )
    (net (code "105") (name "Net-(J666-15)") (class "Default")
      (node (ref "J666") (pin "0") (pinfunction "15_0") (pintype "passive"))
      (node (ref "J667") (pin "0") (pinfunction "16_0") (pintype "passive"))
    )
    (net (code "106") (name "Net-(J666-17)") (class "Default")
      (node (ref "J666") (pin "0") (pinfunction "17_0") (pintype "passive"))
      (node (ref "J667") (pin "0") (pinfunction "18_0") (pintype "passive"))
    )
    (net (code "107") (name "Net-(J666-23)") (class "Default")
      (node (ref "J666") (pin "0") (pinfunction "23_0") (pintype "passive"))
      (node (ref "J667") (pin "0") (pinfunction "24_0") (pintype "passive"))
    )
    (net (code "108") (name "Net-(J666-25)") (class "Default")
      (node (ref "J666") (pin "0") (pinfunction "25_0") (pintype "passive"))
      (node (ref "J667") (pin "0") (pinfunction "26_0") (pintype "passive"))
    )
    (net (code "109") (name "Net-(J666-27)") (class "Default")
      (node (ref "J666") (pin "0") (pinfunction "27_0") (pintype "passive"))
      (node (ref "J667") (pin "0") (pinfunction "28_0") (pintype "passive"))
    )
    (net (code "110") (name "Net-(J666-29)") (class "Default")
      (node (ref "J666") (pin "0") (pinfunction "29_0") (pintype "passive"))
      (node (ref "J667") (pin "0") (pinfunction "30_0") (pintype "passive"))
    )
    (net (code "111") (name "Net-(J666-31)") (class "Default")
      (node (ref "J666") (pin "0") (pinfunction "31_0") (pintype "passive"))
      (node (ref "J667") (pin "0") (pinfunction "32_0") (pintype "passive"))
    )
    (net (code "112") (name "Net-(J666-33)") (class "Default")
      (node (ref "J666") (pin "0") (pinfunction "33_0") (pintype "passive"))
      (node (ref "J667") (pin "0") (pinfunction "34_0") (pintype "passive"))
    )
    (net (code "113") (name "Net-(J666-49)") (class "Default")
      (node (ref "J666") (pin "0") (pinfunction "49_0") (pintype "passive"))
      (node (ref "J667") (pin "0") (pinfunction "50_0") (pintype "passive"))
    )
    (net (code "114") (name "Net-(J666-51)") (class "Default")
      (node (ref "J666") (pin "0") (pinfunction "51_0") (pintype "passive"))
      (node (ref "J667") (pin "0") (pinfunction "52_0") (pintype "passive"))
    )
    (net (code "115") (name "Net-(J666-53)") (class "Default")
      (node (ref "J666") (pin "0") (pinfunction "53_0") (pintype "passive"))
      (node (ref "J667") (pin "0") (pinfunction "54_0") (pintype "passive"))
    )
    (net (code "116") (name "Net-(J666-55)") (class "Default")
      (node (ref "J666") (pin "0") (pinfunction "55_0") (pintype "passive"))
      (node (ref "J667") (pin "0") (pinfunction "56_0") (pintype "passive"))
    )
    (net (code "117") (name "Net-(J666-57)") (class "Default")
      (node (ref "J666") (pin "0") (pinfunction "57_0") (pintype "passive"))
      (node (ref "J667") (pin "0") (pinfunction "58_0") (pintype "passive"))
    )
    (net (code "118") (name "Net-(J668-11)") (class "Default")
      (node (ref "J668") (pin "0") (pinfunction "11_0") (pintype "passive"))
      (node (ref "J669") (pin "0") (pinfunction "12_0") (pintype "passive"))
    )
    (net (code "119") (name "Net-(J668-13)") (class "Default")
      (node (ref "J668") (pin "0") (pinfunction "13_0") (pintype "passive"))
      (node (ref "J669") (pin "0") (pinfunction "14_0") (pintype "passive"))
    )
    (net (code "120") (name "Net-(J668-15)") (class "Default")
      (node (ref "J668") (pin "0") (pinfunction "15_0") (pintype "passive"))
      (node (ref "J669") (pin "0") (pinfunction "16_0") (pintype "passive"))
    )
    (net (code "121") (name "Net-(J668-17)") (class "Default")
      (node (ref "J668") (pin "0") (pinfunction "17_0") (pintype "passive"))
      (node (ref "J669") (pin "0") (pinfunction "18_0") (pintype "passive"))
    )
    (net (code "122") (name "Net-(J668-23)") (class "Default")
      (node (ref "J668") (pin "0") (pinfunction "23_0") (pintype "passive"))
      (node (ref "J669") (pin "0") (pinfunction "24_0") (pintype "passive"))
    )
    (net (code "123") (name "Net-(J668-25)") (class "Default")
      (node (ref "J668") (pin "0") (pinfunction "25_0") (pintype "passive"))
      (node (ref "J669") (pin "0") (pinfunction "26_0") (pintype "passive"))
    )
    (net (code "124") (name "Net-(J668-27)") (class "Default")
      (node (ref "J668") (pin "0") (pinfunction "27_0") (pintype "passive"))
      (node (ref "J669") (pin "0") (pinfunction "28_0") (pintype "passive"))
    )
    (net (code "125") (name "Net-(J668-29)") (class "Default")
      (node (ref "J668") (pin "0") (pinfunction "29_0") (pintype "passive"))
      (node (ref "J669") (pin "0") (pinfunction "30_0") (pintype "passive"))
    )
    (net (code "126") (name "Net-(J668-31)") (class "Default")
      (node (ref "J668") (pin "0") (pinfunction "31_0") (pintype "passive"))
      (node (ref "J669") (pin "0") (pinfunction "32_0") (pintype "passive"))
    )
    (net (code "127") (name "Net-(J668-33)") (class "Default")
      (node (ref "J668") (pin "0") (pinfunction "33_0") (pintype "passive"))
      (node (ref "J669") (pin "0") (pinfunction "34_0") (pintype "passive"))
    )
    (net (code "128") (name "Net-(J668-49)") (class "Default")
      (node (ref "J668") (pin "0") (pinfunction "49_0") (pintype "passive"))
      (node (ref "J669") (pin "0") (pinfunction "50_0") (pintype "passive"))
    )
    (net (code "129") (name "Net-(J668-51)") (class "Default")
      (node (ref "J668") (pin "0") (pinfunction "51_0") (pintype "passive"))
      (node (ref "J669") (pin "0") (pinfunction "52_0") (pintype "passive"))
    )
    (net (code "130") (name "Net-(J668-53)") (class "Default")
      (node (ref "J668") (pin "0") (pinfunction "53_0") (pintype "passive"))
      (node (ref "J669") (pin "0") (pinfunction "54_0") (pintype "passive"))
    )
    (net (code "131") (name "Net-(J668-55)") (class "Default")
      (node (ref "J668") (pin "0") (pinfunction "55_0") (pintype "passive"))
      (node (ref "J669") (pin "0") (pinfunction "56_0") (pintype "passive"))
    )
    (net (code "132") (name "Net-(J668-57)") (class "Default")
      (node (ref "J668") (pin "0") (pinfunction "57_0") (pintype "passive"))
      (node (ref "J669") (pin "0") (pinfunction "58_0") (pintype "passive"))
    )
    (net (code "133") (name "Net-(R701-2)") (class "Default")
      (node (ref "R701") (pin "0") (pinfunction "2_0") (pintype "passive"))
      (node (ref "U601") (pin "0") (pinfunction "FSADJ_0") (pintype "passive"))
    )
    (net (code "134") (name "Net-(R702-2)") (class "Default")
      (node (ref "R702") (pin "0") (pinfunction "2_0") (pintype "passive"))
      (node (ref "U602") (pin "0") (pinfunction "FSADJ_0") (pintype "passive"))
    )
    (net (code "135") (name "unconnected-(J666-6-Pad0)") (class "Default")
      (node (ref "J666") (pin "0") (pinfunction "6_0") (pintype "passive"))
    )
    (net (code "136") (name "unconnected-(J666-8-Pad0)") (class "Default")
      (node (ref "J666") (pin "0") (pinfunction "8_0") (pintype "passive"))
    )
    (net (code "137") (name "unconnected-(J666-10-Pad0)") (class "Default")
      (node (ref "J666") (pin "0") (pinfunction "10_0") (pintype "passive"))
    )
    (net (code "138") (name "unconnected-(J666-12-Pad0)") (class "Default")
      (node (ref "J666") (pin "0") (pinfunction "12_0") (pintype "passive"))
    )
    (net (code "139") (name "unconnected-(J666-14-Pad0)") (class "Default")
      (node (ref "J666") (pin "0") (pinfunction "14_0") (pintype "passive"))
    )
    (net (code "140") (name "unconnected-(J666-16-Pad0)") (class "Default")
      (node (ref "J666") (pin "0") (pinfunction "16_0") (pintype "passive"))
    )
    (net (code "141") (name "unconnected-(J666-18-Pad0)") (class "Default")
      (node (ref "J666") (pin "0") (pinfunction "18_0") (pintype "passive"))
    )
    (net (code "142") (name "unconnected-(J666-20-Pad0)") (class "Default")
      (node (ref "J666") (pin "0") (pinfunction "20_0") (pintype "passive"))
    )
    (net (code "143") (name "unconnected-(J666-22-Pad0)") (class "Default")
      (node (ref "J666") (pin "0") (pinfunction "22_0") (pintype "passive"))
    )
    (net (code "144") (name "unconnected-(J666-24-Pad0)") (class "Default")
      (node (ref "J666") (pin "0") (pinfunction "24_0") (pintype "passive"))
    )
    (net (code "145") (name "unconnected-(J666-26-Pad0)") (class "Default")
      (node (ref "J666") (pin "0") (pinfunction "26_0") (pintype "passive"))
    )
    (net (code "146") (name "unconnected-(J666-28-Pad0)") (class "Default")
      (node (ref "J666") (pin "0") (pinfunction "28_0") (pintype "passive"))
    )
    (net (code "147") (name "unconnected-(J666-30-Pad0)") (class "Default")
      (node (ref "J666") (pin "0") (pinfunction "30_0") (pintype "passive"))
    )
    (net (code "148") (name "unconnected-(J666-32-Pad0)") (class "Default")
      (node (ref "J666") (pin "0") (pinfunction "32_0") (pintype "passive"))
    )
    (net (code "149") (name "unconnected-(J666-34-Pad0)") (class "Default")
      (node (ref "J666") (pin "0") (pinfunction "34_0") (pintype "passive"))
    )
    (net (code "150") (name "unconnected-(J666-35-Pad0)") (class "Default")
      (node (ref "J666") (pin "0") (pinfunction "35_0") (pintype "passive"))
    )
    (net (code "151") (name "unconnected-(J666-36-Pad0)") (class "Default")
      (node (ref "J666") (pin "0") (pinfunction "36_0") (pintype "passive"))
    )
    (net (code "152") (name "unconnected-(J666-39-Pad0)") (class "Default")
      (node (ref "J666") (pin "0") (pinfunction "39_0") (pintype "passive"))
    )
    (net (code "153") (name "unconnected-(J666-40-Pad0)") (class "Default")
      (node (ref "J666") (pin "0") (pinfunction "40_0") (pintype "passive"))
    )
    (net (code "154") (name "unconnected-(J666-50-Pad0)") (class "Default")
      (node (ref "J666") (pin "0") (pinfunction "50_0") (pintype "passive"))
    )
    (net (code "155") (name "unconnected-(J666-52-Pad0)") (class "Default")
      (node (ref "J666") (pin "0") (pinfunction "52_0") (pintype "passive"))
    )
    (net (code "156") (name "unconnected-(J666-56-Pad0)") (class "Default")
      (node (ref "J666") (pin "0") (pinfunction "56_0") (pintype "passive"))
    )
    (net (code "157") (name "unconnected-(J666-59-Pad0)") (class "Default")
      (node (ref "J666") (pin "0") (pinfunction "59_0") (pintype "passive"))
    )
    (net (code "158") (name "unconnected-(J666-60-Pad0)") (class "Default")
      (node (ref "J666") (pin "0") (pinfunction "60_0") (pintype "passive"))
    )
    (net (code "159") (name "unconnected-(J666-61-Pad0)") (class "Default")
      (node (ref "J666") (pin "0") (pinfunction "61_0") (pintype "passive"))
    )
    (net (code "160") (name "unconnected-(J666-62-Pad0)") (class "Default")
      (node (ref "J666") (pin "0") (pinfunction "62_0") (pintype "passive"))
    )
    (net (code "161") (name "unconnected-(J667-5-Pad0)") (class "Default")
      (node (ref "J667") (pin "0") (pinfunction "5_0") (pintype "passive"))
    )
    (net (code "162") (name "unconnected-(J667-7-Pad0)") (class "Default")
      (node (ref "J667") (pin "0") (pinfunction "7_0") (pintype "passive"))
    )
    (net (code "163") (name "unconnected-(J667-9-Pad0)") (class "Default")
      (node (ref "J667") (pin "0") (pinfunction "9_0") (pintype "passive"))
    )
    (net (code "164") (name "unconnected-(J667-11-Pad0)") (class "Default")
      (node (ref "J667") (pin "0") (pinfunction "11_0") (pintype "passive"))
    )
    (net (code "165") (name "unconnected-(J667-13-Pad0)") (class "Default")
      (node (ref "J667") (pin "0") (pinfunction "13_0") (pintype "passive"))
    )
    (net (code "166") (name "unconnected-(J667-15-Pad0)") (class "Default")
      (node (ref "J667") (pin "0") (pinfunction "15_0") (pintype "passive"))
    )
    (net (code "167") (name "unconnected-(J667-17-Pad0)") (class "Default")
      (node (ref "J667") (pin "0") (pinfunction "17_0") (pintype "passive"))
    )
    (net (code "168") (name "unconnected-(J667-19-Pad0)") (class "Default")
      (node (ref "J667") (pin "0") (pinfunction "19_0") (pintype "passive"))
    )
    (net (code "169") (name "unconnected-(J667-21-Pad0)") (class "Default")
      (node (ref "J667") (pin "0") (pinfunction "21_0") (pintype "passive"))
    )
    (net (code "170") (name "unconnected-(J667-23-Pad0)") (class "Default")
      (node (ref "J667") (pin "0") (pinfunction "23_0") (pintype "passive"))
    )
    (net (code "171") (name "unconnected-(J667-25-Pad0)") (class "Default")
      (node (ref "J667") (pin "0") (pinfunction "25_0") (pintype "passive"))
    )
    (net (code "172") (name "unconnected-(J667-27-Pad0)") (class "Default")
      (node (ref "J667") (pin "0") (pinfunction "27_0") (pintype "passive"))
    )
    (net (code "173") (name "unconnected-(J667-29-Pad0)") (class "Default")
      (node (ref "J667") (pin "0") (pinfunction "29_0") (pintype "passive"))
    )
    (net (code "174") (name "unconnected-(J667-31-Pad0)") (class "Default")
      (node (ref "J667") (pin "0") (pinfunction "31_0") (pintype "passive"))
    )
    (net (code "175") (name "unconnected-(J667-33-Pad0)") (class "Default")
      (node (ref "J667") (pin "0") (pinfunction "33_0") (pintype "passive"))
    )
    (net (code "176") (name "unconnected-(J667-35-Pad0)") (class "Default")
      (node (ref "J667") (pin "0") (pinfunction "35_0") (pintype "passive"))
    )
    (net (code "177") (name "unconnected-(J667-36-Pad0)") (class "Default")
      (node (ref "J667") (pin "0") (pinfunction "36_0") (pintype "passive"))
    )
    (net (code "178") (name "unconnected-(J667-39-Pad0)") (class "Default")
      (node (ref "J667") (pin "0") (pinfunction "39_0") (pintype "passive"))
    )
    (net (code "179") (name "unconnected-(J667-40-Pad0)") (class "Default")
      (node (ref "J667") (pin "0") (pinfunction "40_0") (pintype "passive"))
    )
    (net (code "180") (name "unconnected-(J667-49-Pad0)") (class "Default")
      (node (ref "J667") (pin "0") (pinfunction "49_0") (pintype "passive"))
    )
    (net (code "181") (name "unconnected-(J667-51-Pad0)") (class "Default")
      (node (ref "J667") (pin "0") (pinfunction "51_0") (pintype "passive"))
    )
    (net (code "182") (name "unconnected-(J667-55-Pad0)") (class "Default")
      (node (ref "J667") (pin "0") (pinfunction "55_0") (pintype "passive"))
    )
    (net (code "183") (name "unconnected-(J667-59-Pad0)") (class "Default")
      (node (ref "J667") (pin "0") (pinfunction "59_0") (pintype "passive"))
    )
    (net (code "184") (name "unconnected-(J667-60-Pad0)") (class "Default")
      (node (ref "J667") (pin "0") (pinfunction "60_0") (pintype "passive"))
    )
    (net (code "185") (name "unconnected-(J667-61-Pad0)") (class "Default")
      (node (ref "J667") (pin "0") (pinfunction "61_0") (pintype "passive"))
    )
    (net (code "186") (name "unconnected-(J667-62-Pad0)") (class "Default")
      (node (ref "J667") (pin "0") (pinfunction "62_0") (pintype "passive"))
    )
    (net (code "187") (name "unconnected-(J668-6-Pad0)") (class "Default")
      (node (ref "J668") (pin "0") (pinfunction "6_0") (pintype "passive"))
    )
    (net (code "188") (name "unconnected-(J668-8-Pad0)") (class "Default")
      (node (ref "J668") (pin "0") (pinfunction "8_0") (pintype "passive"))
    )
    (net (code "189") (name "unconnected-(J668-10-Pad0)") (class "Default")
      (node (ref "J668") (pin "0") (pinfunction "10_0") (pintype "passive"))
    )
    (net (code "190") (name "unconnected-(J668-12-Pad0)") (class "Default")
      (node (ref "J668") (pin "0") (pinfunction "12_0") (pintype "passive"))
    )
    (net (code "191") (name "unconnected-(J668-14-Pad0)") (class "Default")
      (node (ref "J668") (pin "0") (pinfunction "14_0") (pintype "passive"))
    )
    (net (code "192") (name "unconnected-(J668-16-Pad0)") (class "Default")
      (node (ref "J668") (pin "0") (pinfunction "16_0") (pintype "passive"))
    )
    (net (code "193") (name "unconnected-(J668-18-Pad0)") (class "Default")
      (node (ref "J668") (pin "0") (pinfunction "18_0") (pintype "passive"))
    )
    (net (code "194") (name "unconnected-(J668-20-Pad0)") (class "Default")
      (node (ref "J668") (pin "0") (pinfunction "20_0") (pintype "passive"))
    )
    (net (code "195") (name "unconnected-(J668-22-Pad0)") (class "Default")
      (node (ref "J668") (pin "0") (pinfunction "22_0") (pintype "passive"))
    )
    (net (code "196") (name "unconnected-(J668-24-Pad0)") (class "Default")
      (node (ref "J668") (pin "0") (pinfunction "24_0") (pintype "passive"))
    )
    (net (code "197") (name "unconnected-(J668-26-Pad0)") (class "Default")
      (node (ref "J668") (pin "0") (pinfunction "26_0") (pintype "passive"))
    )
    (net (code "198") (name "unconnected-(J668-28-Pad0)") (class "Default")
      (node (ref "J668") (pin "0") (pinfunction "28_0") (pintype "passive"))
    )
    (net (code "199") (name "unconnected-(J668-30-Pad0)") (class "Default")
      (node (ref "J668") (pin "0") (pinfunction "30_0") (pintype "passive"))
    )
    (net (code "200") (name "unconnected-(J668-32-Pad0)") (class "Default")
      (node (ref "J668") (pin "0") (pinfunction "32_0") (pintype "passive"))
    )
    (net (code "201") (name "unconnected-(J668-34-Pad0)") (class "Default")
      (node (ref "J668") (pin "0") (pinfunction "34_0") (pintype "passive"))
    )
    (net (code "202") (name "unconnected-(J668-35-Pad0)") (class "Default")
      (node (ref "J668") (pin "0") (pinfunction "35_0") (pintype "passive"))
    )
    (net (code "203") (name "unconnected-(J668-36-Pad0)") (class "Default")
      (node (ref "J668") (pin "0") (pinfunction "36_0") (pintype "passive"))
    )
    (net (code "204") (name "unconnected-(J668-39-Pad0)") (class "Default")
      (node (ref "J668") (pin "0") (pinfunction "39_0") (pintype "passive"))
    )
    (net (code "205") (name "unconnected-(J668-40-Pad0)") (class "Default")
      (node (ref "J668") (pin "0") (pinfunction "40_0") (pintype "passive"))
    )
    (net (code "206") (name "unconnected-(J668-50-Pad0)") (class "Default")
      (node (ref "J668") (pin "0") (pinfunction "50_0") (pintype "passive"))
    )
    (net (code "207") (name "unconnected-(J668-52-Pad0)") (class "Default")
      (node (ref "J668") (pin "0") (pinfunction "52_0") (pintype "passive"))
    )
    (net (code "208") (name "unconnected-(J668-56-Pad0)") (class "Default")
      (node (ref "J668") (pin "0") (pinfunction "56_0") (pintype "passive"))
    )
    (net (code "209") (name "unconnected-(J668-59-Pad0)") (class "Default")
      (node (ref "J668") (pin "0") (pinfunction "59_0") (pintype "passive"))
    )
    (net (code "210") (name "unconnected-(J668-60-Pad0)") (class "Default")
      (node (ref "J668") (pin "0") (pinfunction "60_0") (pintype "passive"))
    )
    (net (code "211") (name "unconnected-(J668-61-Pad0)") (class "Default")
      (node (ref "J668") (pin "0") (pinfunction "61_0") (pintype "passive"))
    )
    (net (code "212") (name "unconnected-(J668-62-Pad0)") (class "Default")
      (node (ref "J668") (pin "0") (pinfunction "62_0") (pintype "passive"))
    )
    (net (code "213") (name "unconnected-(J669-5-Pad0)") (class "Default")
      (node (ref "J669") (pin "0") (pinfunction "5_0") (pintype "passive"))
    )
    (net (code "214") (name "unconnected-(J669-7-Pad0)") (class "Default")
      (node (ref "J669") (pin "0") (pinfunction "7_0") (pintype "passive"))
    )
    (net (code "215") (name "unconnected-(J669-9-Pad0)") (class "Default")
      (node (ref "J669") (pin "0") (pinfunction "9_0") (pintype "passive"))
    )
    (net (code "216") (name "unconnected-(J669-11-Pad0)") (class "Default")
      (node (ref "J669") (pin "0") (pinfunction "11_0") (pintype "passive"))
    )
    (net (code "217") (name "unconnected-(J669-13-Pad0)") (class "Default")
      (node (ref "J669") (pin "0") (pinfunction "13_0") (pintype "passive"))
    )
    (net (code "218") (name "unconnected-(J669-15-Pad0)") (class "Default")
      (node (ref "J669") (pin "0") (pinfunction "15_0") (pintype "passive"))
    )
    (net (code "219") (name "unconnected-(J669-17-Pad0)") (class "Default")
      (node (ref "J669") (pin "0") (pinfunction "17_0") (pintype "passive"))
    )
    (net (code "220") (name "unconnected-(J669-19-Pad0)") (class "Default")
      (node (ref "J669") (pin "0") (pinfunction "19_0") (pintype "passive"))
    )
    (net (code "221") (name "unconnected-(J669-21-Pad0)") (class "Default")
      (node (ref "J669") (pin "0") (pinfunction "21_0") (pintype "passive"))
    )
    (net (code "222") (name "unconnected-(J669-23-Pad0)") (class "Default")
      (node (ref "J669") (pin "0") (pinfunction "23_0") (pintype "passive"))
    )
    (net (code "223") (name "unconnected-(J669-25-Pad0)") (class "Default")
      (node (ref "J669") (pin "0") (pinfunction "25_0") (pintype "passive"))
    )
    (net (code "224") (name "unconnected-(J669-27-Pad0)") (class "Default")
      (node (ref "J669") (pin "0") (pinfunction "27_0") (pintype "passive"))
    )
    (net (code "225") (name "unconnected-(J669-29-Pad0)") (class "Default")
      (node (ref "J669") (pin "0") (pinfunction "29_0") (pintype "passive"))
    )
    (net (code "226") (name "unconnected-(J669-31-Pad0)") (class "Default")
      (node (ref "J669") (pin "0") (pinfunction "31_0") (pintype "passive"))
    )
    (net (code "227") (name "unconnected-(J669-33-Pad0)") (class "Default")
      (node (ref "J669") (pin "0") (pinfunction "33_0") (pintype "passive"))
    )
    (net (code "228") (name "unconnected-(J669-35-Pad0)") (class "Default")
      (node (ref "J669") (pin "0") (pinfunction "35_0") (pintype "passive"))
    )
    (net (code "229") (name "unconnected-(J669-36-Pad0)") (class "Default")
      (node (ref "J669") (pin "0") (pinfunction "36_0") (pintype "passive"))
    )
    (net (code "230") (name "unconnected-(J669-39-Pad0)") (class "Default")
      (node (ref "J669") (pin "0") (pinfunction "39_0") (pintype "passive"))
    )
    (net (code "231") (name "unconnected-(J669-40-Pad0)") (class "Default")
      (node (ref "J669") (pin "0") (pinfunction "40_0") (pintype "passive"))
    )
    (net (code "232") (name "unconnected-(J669-49-Pad0)") (class "Default")
      (node (ref "J669") (pin "0") (pinfunction "49_0") (pintype "passive"))
    )
    (net (code "233") (name "unconnected-(J669-51-Pad0)") (class "Default")
      (node (ref "J669") (pin "0") (pinfunction "51_0") (pintype "passive"))
    )
    (net (code "234") (name "unconnected-(J669-55-Pad0)") (class "Default")
      (node (ref "J669") (pin "0") (pinfunction "55_0") (pintype "passive"))
    )
    (net (code "235") (name "unconnected-(J669-59-Pad0)") (class "Default")
      (node (ref "J669") (pin "0") (pinfunction "59_0") (pintype "passive"))
    )
    (net (code "236") (name "unconnected-(J669-60-Pad0)") (class "Default")
      (node (ref "J669") (pin "0") (pinfunction "60_0") (pintype "passive"))
    )
    (net (code "237") (name "unconnected-(J669-61-Pad0)") (class "Default")
      (node (ref "J669") (pin "0") (pinfunction "61_0") (pintype "passive"))
    )
    (net (code "238") (name "unconnected-(J669-62-Pad0)") (class "Default")
      (node (ref "J669") (pin "0") (pinfunction "62_0") (pintype "passive"))
    )
    (net (code "239") (name "unconnected-(R1001-1-Pad0)") (class "Default")
      (node (ref "R1001") (pin "0") (pinfunction "1_0") (pintype "passive"))
    )
    (net (code "240") (name "unconnected-(R1003-1-Pad0)") (class "Default")
      (node (ref "R1003") (pin "0") (pinfunction "1_0") (pintype "passive"))
    )
    (net (code "241") (name "unconnected-(U601-39-AUX_ADC_A1-Pad0)") (class "Default")
      (node (ref "U601-39") (pin "0") (pinfunction "AUX_ADC_A1_0") (pintype "passive"))
    )
    (net (code "242") (name "unconnected-(U601-39-AUX_ADC_A2-Pad0)") (class "Default")
      (node (ref "U601-39") (pin "0") (pinfunction "AUX_ADC_A2_0") (pintype "passive"))
    )
    (net (code "243") (name "unconnected-(U601-39-AUX_ADC_B1-Pad0)") (class "Default")
      (node (ref "U601-39") (pin "0") (pinfunction "AUX_ADC_B1_0") (pintype "passive"))
    )
    (net (code "244") (name "unconnected-(U601-39-AUX_ADC_B2-Pad0)") (class "Default")
      (node (ref "U601-39") (pin "0") (pinfunction "AUX_ADC_B2_0") (pintype "passive"))
    )
    (net (code "245") (name "unconnected-(U601-39-AUX_ADC_REF-Pad0)") (class "Default")
      (node (ref "U601-39") (pin "0") (pinfunction "AUX_ADC_REF_0") (pintype "passive"))
    )
    (net (code "246") (name "unconnected-(U601-39-AUX_DAC_A-Pad0)") (class "Default")
      (node (ref "U601-39") (pin "0") (pinfunction "AUX_DAC_A_0") (pintype "passive"))
    )
    (net (code "247") (name "unconnected-(U601-39-AUX_DAC_B-Pad0)") (class "Default")
      (node (ref "U601-39") (pin "0") (pinfunction "AUX_DAC_B_0") (pintype "passive"))
    )
    (net (code "248") (name "unconnected-(U601-39-AUX_DAC_C-Pad0)") (class "Default")
      (node (ref "U601-39") (pin "0") (pinfunction "AUX_DAC_C_0") (pintype "passive"))
    )
    (net (code "249") (name "unconnected-(U601-39-SIGDELT-Pad0)") (class "Default")
      (node (ref "U601-39") (pin "0") (pinfunction "SIGDELT_0") (pintype "passive"))
    )
    (net (code "250") (name "unconnected-(U601-40-AUX_SPI_CLK-Pad0)") (class "Default")
      (node (ref "U601-40") (pin "0") (pinfunction "AUX_SPI_CLK_0") (pintype "passive"))
    )
    (net (code "251") (name "unconnected-(U601-40-AUX_SPI_CSB-Pad0)") (class "Default")
      (node (ref "U601-40") (pin "0") (pinfunction "AUX_SPI_CSB_0") (pintype "passive"))
    )
    (net (code "252") (name "unconnected-(U601-40-AUX_SPI_DO-Pad0)") (class "Default")
      (node (ref "U601-40") (pin "0") (pinfunction "AUX_SPI_DO_0") (pintype "passive"))
    )
    (net (code "253") (name "unconnected-(U601-40-RESETB-Pad0)") (class "Default")
      (node (ref "U601-40") (pin "0") (pinfunction "RESETB_0") (pintype "passive"))
    )
    (net (code "254") (name "unconnected-(U601-40-SCLK-Pad0)") (class "Default")
      (node (ref "U601-40") (pin "0") (pinfunction "SCLK_0") (pintype "passive"))
    )
    (net (code "255") (name "unconnected-(U601-40-SDIO-Pad0)") (class "Default")
      (node (ref "U601-40") (pin "0") (pinfunction "SDIO_0") (pintype "passive"))
    )
    (net (code "256") (name "unconnected-(U601-40-SDO-Pad0)") (class "Default")
      (node (ref "U601-40") (pin "0") (pinfunction "SDO_0") (pintype "passive"))
    )
    (net (code "257") (name "unconnected-(U601-40-SEN-Pad0)") (class "Default")
      (node (ref "U601-40") (pin "0") (pinfunction "SEN_0") (pintype "passive"))
    )
    (net (code "258") (name "unconnected-(U602-0-AUX_ADC_A1-Pad0)") (class "Default")
      (node (ref "U602-0") (pin "0") (pinfunction "AUX_ADC_A1_0") (pintype "passive"))
    )
    (net (code "259") (name "unconnected-(U602-0-AUX_ADC_A2-Pad0)") (class "Default")
      (node (ref "U602-0") (pin "0") (pinfunction "AUX_ADC_A2_0") (pintype "passive"))
    )
    (net (code "260") (name "unconnected-(U602-0-AUX_ADC_B1-Pad0)") (class "Default")
      (node (ref "U602-0") (pin "0") (pinfunction "AUX_ADC_B1_0") (pintype "passive"))
    )
    (net (code "261") (name "unconnected-(U602-0-AUX_ADC_B2-Pad0)") (class "Default")
      (node (ref "U602-0") (pin "0") (pinfunction "AUX_ADC_B2_0") (pintype "passive"))
    )
    (net (code "262") (name "unconnected-(U602-0-AUX_ADC_REF-Pad0)") (class "Default")
      (node (ref "U602-0") (pin "0") (pinfunction "AUX_ADC_REF_0") (pintype "passive"))
    )
    (net (code "263") (name "unconnected-(U602-0-AUX_DAC_A-Pad0)") (class "Default")
      (node (ref "U602-0") (pin "0") (pinfunction "AUX_DAC_A_0") (pintype "passive"))
    )
    (net (code "264") (name "unconnected-(U602-0-AUX_DAC_B-Pad0)") (class "Default")
      (node (ref "U602-0") (pin "0") (pinfunction "AUX_DAC_B_0") (pintype "passive"))
    )
    (net (code "265") (name "unconnected-(U602-0-AUX_DAC_C-Pad0)") (class "Default")
      (node (ref "U602-0") (pin "0") (pinfunction "AUX_DAC_C_0") (pintype "passive"))
    )
    (net (code "266") (name "unconnected-(U602-0-SIGDELT-Pad0)") (class "Default")
      (node (ref "U602-0") (pin "0") (pinfunction "SIGDELT_0") (pintype "passive"))
    )
    (net (code "267") (name "unconnected-(U602-1-AUX_SPI_CLK-Pad0)") (class "Default")
      (node (ref "U602-1") (pin "0") (pinfunction "AUX_SPI_CLK_0") (pintype "passive"))
    )
    (net (code "268") (name "unconnected-(U602-1-AUX_SPI_CSB-Pad0)") (class "Default")
      (node (ref "U602-1") (pin "0") (pinfunction "AUX_SPI_CSB_0") (pintype "passive"))
    )
    (net (code "269") (name "unconnected-(U602-1-AUX_SPI_DO-Pad0)") (class "Default")
      (node (ref "U602-1") (pin "0") (pinfunction "AUX_SPI_DO_0") (pintype "passive"))
    )
    (net (code "270") (name "unconnected-(U602-1-RESETB-Pad0)") (class "Default")
      (node (ref "U602-1") (pin "0") (pinfunction "RESETB_0") (pintype "passive"))
    )
    (net (code "271") (name "unconnected-(U602-1-SCLK-Pad0)") (class "Default")
      (node (ref "U602-1") (pin "0") (pinfunction "SCLK_0") (pintype "passive"))
    )
    (net (code "272") (name "unconnected-(U602-1-SDIO-Pad0)") (class "Default")
      (node (ref "U602-1") (pin "0") (pinfunction "SDIO_0") (pintype "passive"))
    )
    (net (code "273") (name "unconnected-(U602-1-SDO-Pad0)") (class "Default")
      (node (ref "U602-1") (pin "0") (pinfunction "SDO_0") (pintype "passive"))
    )
    (net (code "274") (name "unconnected-(U602-1-SEN-Pad0)") (class "Default")
      (node (ref "U602-1") (pin "0") (pinfunction "SEN_0") (pintype "passive"))
    )
  )
)
